# H27U1G8F2BTR-BC.net
KiCad netlist of a schematic drawn in Altium Designer
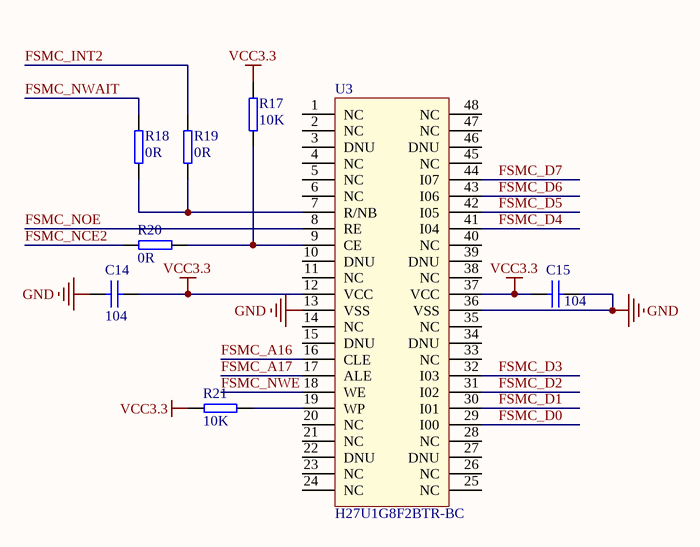
[diagram p0: H27U1G8F2BTR-BC.SchDoc]

(export (version "E")
  (design (tool "Eeschema 10.0.6"))
  (components
    (comp (ref "C14")
      (value "104")
      (footprint "0805C")
      (description "贴片电容")
      (libsource (lib "常用元件") (part "Cap"))
    )
    (comp (ref "C15")
      (value "104")
      (footprint "0805C")
      (description "贴片电容")
      (libsource (lib "常用元件") (part "Cap"))
    )
    (comp (ref "R17") (value "10K") (footprint "2512R") (libsource (lib "常用元件") (part "RES-10K")))
    (comp (ref "R18") (value "0R") (footprint "2512R") (libsource (lib "常用元件") (part "RES-10K")))
    (comp (ref "R19") (value "0R") (footprint "2512R") (libsource (lib "常用元件") (part "RES-10K")))
    (comp (ref "R20") (value "0R") (footprint "2512R") (libsource (lib "常用元件") (part "RES-10K")))
    (comp (ref "R21") (value "10K") (footprint "2512R") (libsource (lib "常用元件") (part "RES-10K")))
    (comp (ref "U3")
      (value "H27U1G8F2BTR-BC")
      (footprint "TSOP48")
      (description "128M字节Nand Flash")
      (libsource (lib "常用元件") (part "H27U1G8F2BTR-BC"))
    )
  )
  (nets
    (net (code "1") (name "/FSMC_A16") (class "Default")
      (node (ref "U3") (pin "16") (pinfunction "CLE_16") (pintype "passive"))
    )
    (net (code "2") (name "/FSMC_A17") (class "Default")
      (node (ref "U3") (pin "17") (pinfunction "ALE_17") (pintype "passive"))
    )
    (net (code "3") (name "/FSMC_D0") (class "Default")
      (node (ref "U3") (pin "29") (pinfunction "I00_29") (pintype "passive"))
    )
    (net (code "4") (name "/FSMC_D1") (class "Default")
      (node (ref "U3") (pin "30") (pinfunction "I01_30") (pintype "passive"))
    )
    (net (code "5") (name "/FSMC_D2") (class "Default")
      (node (ref "U3") (pin "31") (pinfunction "I02_31") (pintype "passive"))
    )
    (net (code "6") (name "/FSMC_D3") (class "Default")
      (node (ref "U3") (pin "32") (pinfunction "I03_32") (pintype "passive"))
    )
    (net (code "7") (name "/FSMC_D4") (class "Default")
      (node (ref "U3") (pin "41") (pinfunction "I04_41") (pintype "passive"))
    )
    (net (code "8") (name "/FSMC_D5") (class "Default")
      (node (ref "U3") (pin "42") (pinfunction "I05_42") (pintype "passive"))
    )
    (net (code "9") (name "/FSMC_D6") (class "Default")
      (node (ref "U3") (pin "43") (pinfunction "I06_43") (pintype "passive"))
    )
    (net (code "10") (name "/FSMC_D7") (class "Default")
      (node (ref "U3") (pin "44") (pinfunction "I07_44") (pintype "passive"))
    )
    (net (code "11") (name "/FSMC_INT2") (class "Default")
      (node (ref "R19") (pin "2") (pinfunction "2_2") (pintype "passive"))
    )
    (net (code "12") (name "/FSMC_NCE2") (class "Default")
      (node (ref "R20") (pin "1") (pinfunction "1_1") (pintype "passive"))
    )
    (net (code "13") (name "/FSMC_NOE") (class "Default")
      (node (ref "U3") (pin "8") (pinfunction "RE_8") (pintype "passive"))
    )
    (net (code "14") (name "/FSMC_NWAIT") (class "Default")
      (node (ref "R18") (pin "2") (pinfunction "2_2") (pintype "passive"))
    )
    (net (code "15") (name "/FSMC_NWE") (class "Default")
      (node (ref "U3") (pin "18") (pinfunction "WE_18") (pintype "passive"))
    )
    (net (code "16") (name "GND") (class "Default")
      (node (ref "C14") (pin "1") (pinfunction "1_1") (pintype "passive"))
      (node (ref "C15") (pin "2") (pinfunction "2_2") (pintype "passive"))
      (node (ref "U3") (pin "13") (pinfunction "VSS_13") (pintype "passive"))
      (node (ref "U3") (pin "36") (pinfunction "VSS_36") (pintype "passive"))
    )
    (net (code "17") (name "Net-(U3-CE)") (class "Default")
      (node (ref "R17") (pin "1") (pinfunction "1_1") (pintype "passive"))
      (node (ref "R20") (pin "2") (pinfunction "2_2") (pintype "passive"))
      (node (ref "U3") (pin "9") (pinfunction "CE_9") (pintype "passive"))
    )
    (net (code "18") (name "Net-(U3-R{slash}NB)") (class "Default")
      (node (ref "R18") (pin "1") (pinfunction "1_1") (pintype "passive"))
      (node (ref "R19") (pin "1") (pinfunction "1_1") (pintype "passive"))
      (node (ref "U3") (pin "7") (pinfunction "R/NB_7") (pintype "passive"))
    )
    (net (code "19") (name "Net-(U3-WP)") (class "Default")
      (node (ref "R21") (pin "2") (pinfunction "2_2") (pintype "passive"))
      (node (ref "U3") (pin "19") (pinfunction "WP_19") (pintype "passive"))
    )
    (net (code "20") (name "VCC3.3") (class "Default")
      (node (ref "C14") (pin "2") (pinfunction "2_2") (pintype "passive"))
      (node (ref "C15") (pin "1") (pinfunction "1_1") (pintype "passive"))
      (node (ref "R17") (pin "2") (pinfunction "2_2") (pintype "passive"))
      (node (ref "R21") (pin "1") (pinfunction "1_1") (pintype "passive"))
      (node (ref "U3") (pin "12") (pinfunction "VCC_12") (pintype "passive"))
      (node (ref "U3") (pin "37") (pinfunction "VCC_37") (pintype "passive"))
    )
    (net (code "21") (name "unconnected-(U3-DNU-Pad3)") (class "Default")
      (node (ref "U3") (pin "3") (pinfunction "DNU_3") (pintype "passive"))
    )
    (net (code "22") (name "unconnected-(U3-DNU-Pad10)") (class "Default")
      (node (ref "U3") (pin "10") (pinfunction "DNU_10") (pintype "passive"))
    )
    (net (code "23") (name "unconnected-(U3-DNU-Pad15)") (class "Default")
      (node (ref "U3") (pin "15") (pinfunction "DNU_15") (pintype "passive"))
    )
    (net (code "24") (name "unconnected-(U3-DNU-Pad22)") (class "Default")
      (node (ref "U3") (pin "22") (pinfunction "DNU_22") (pintype "passive"))
    )
    (net (code "25") (name "unconnected-(U3-DNU-Pad27)") (class "Default")
      (node (ref "U3") (pin "27") (pinfunction "DNU_27") (pintype "passive"))
    )
    (net (code "26") (name "unconnected-(U3-DNU-Pad34)") (class "Default")
      (node (ref "U3") (pin "34") (pinfunction "DNU_34") (pintype "passive"))
    )
    (net (code "27") (name "unconnected-(U3-DNU-Pad39)") (class "Default")
      (node (ref "U3") (pin "39") (pinfunction "DNU_39") (pintype "passive"))
    )
    (net (code "28") (name "unconnected-(U3-DNU-Pad46)") (class "Default")
      (node (ref "U3") (pin "46") (pinfunction "DNU_46") (pintype "passive"))
    )
    (net (code "29") (name "unconnected-(U3-NC-Pad1)") (class "Default")
      (node (ref "U3") (pin "1") (pinfunction "NC_1") (pintype "passive"))
    )
    (net (code "30") (name "unconnected-(U3-NC-Pad2)") (class "Default")
      (node (ref "U3") (pin "2") (pinfunction "NC_2") (pintype "passive"))
    )
    (net (code "31") (name "unconnected-(U3-NC-Pad4)") (class "Default")
      (node (ref "U3") (pin "4") (pinfunction "NC_4") (pintype "passive"))
    )
    (net (code "32") (name "unconnected-(U3-NC-Pad5)") (class "Default")
      (node (ref "U3") (pin "5") (pinfunction "NC_5") (pintype "passive"))
    )
    (net (code "33") (name "unconnected-(U3-NC-Pad6)") (class "Default")
      (node (ref "U3") (pin "6") (pinfunction "NC_6") (pintype "passive"))
    )
    (net (code "34") (name "unconnected-(U3-NC-Pad11)") (class "Default")
      (node (ref "U3") (pin "11") (pinfunction "NC_11") (pintype "passive"))
    )
    (net (code "35") (name "unconnected-(U3-NC-Pad14)") (class "Default")
      (node (ref "U3") (pin "14") (pinfunction "NC_14") (pintype "passive"))
    )
    (net (code "36") (name "unconnected-(U3-NC-Pad20)") (class "Default")
      (node (ref "U3") (pin "20") (pinfunction "NC_20") (pintype "passive"))
    )
    (net (code "37") (name "unconnected-(U3-NC-Pad21)") (class "Default")
      (node (ref "U3") (pin "21") (pinfunction "NC_21") (pintype "passive"))
    )
    (net (code "38") (name "unconnected-(U3-NC-Pad23)") (class "Default")
      (node (ref "U3") (pin "23") (pinfunction "NC_23") (pintype "passive"))
    )
    (net (code "39") (name "unconnected-(U3-NC-Pad24)") (class "Default")
      (node (ref "U3") (pin "24") (pinfunction "NC_24") (pintype "passive"))
    )
    (net (code "40") (name "unconnected-(U3-NC-Pad25)") (class "Default")
      (node (ref "U3") (pin "25") (pinfunction "NC_25") (pintype "passive"))
    )
    (net (code "41") (name "unconnected-(U3-NC-Pad26)") (class "Default")
      (node (ref "U3") (pin "26") (pinfunction "NC_26") (pintype "passive"))
    )
    (net (code "42") (name "unconnected-(U3-NC-Pad28)") (class "Default")
      (node (ref "U3") (pin "28") (pinfunction "NC_28") (pintype "passive"))
    )
    (net (code "43") (name "unconnected-(U3-NC-Pad33)") (class "Default")
      (node (ref "U3") (pin "33") (pinfunction "NC_33") (pintype "passive"))
    )
    (net (code "44") (name "unconnected-(U3-NC-Pad35)") (class "Default")
      (node (ref "U3") (pin "35") (pinfunction "NC_35") (pintype "passive"))
    )
    (net (code "45") (name "unconnected-(U3-NC-Pad38)") (class "Default")
      (node (ref "U3") (pin "38") (pinfunction "NC_38") (pintype "passive"))
    )
    (net (code "46") (name "unconnected-(U3-NC-Pad40)") (class "Default")
      (node (ref "U3") (pin "40") (pinfunction "NC_40") (pintype "passive"))
    )
    (net (code "47") (name "unconnected-(U3-NC-Pad45)") (class "Default")
      (node (ref "U3") (pin "45") (pinfunction "NC_45") (pintype "passive"))
    )
    (net (code "48") (name "unconnected-(U3-NC-Pad47)") (class "Default")
      (node (ref "U3") (pin "47") (pinfunction "NC_47") (pintype "passive"))
    )
    (net (code "49") (name "unconnected-(U3-NC-Pad48)") (class "Default")
      (node (ref "U3") (pin "48") (pinfunction "NC_48") (pintype "passive"))
    )
  )
)
